# Sensor_Board_B.net
KiCad netlist of a schematic drawn in EAGLE
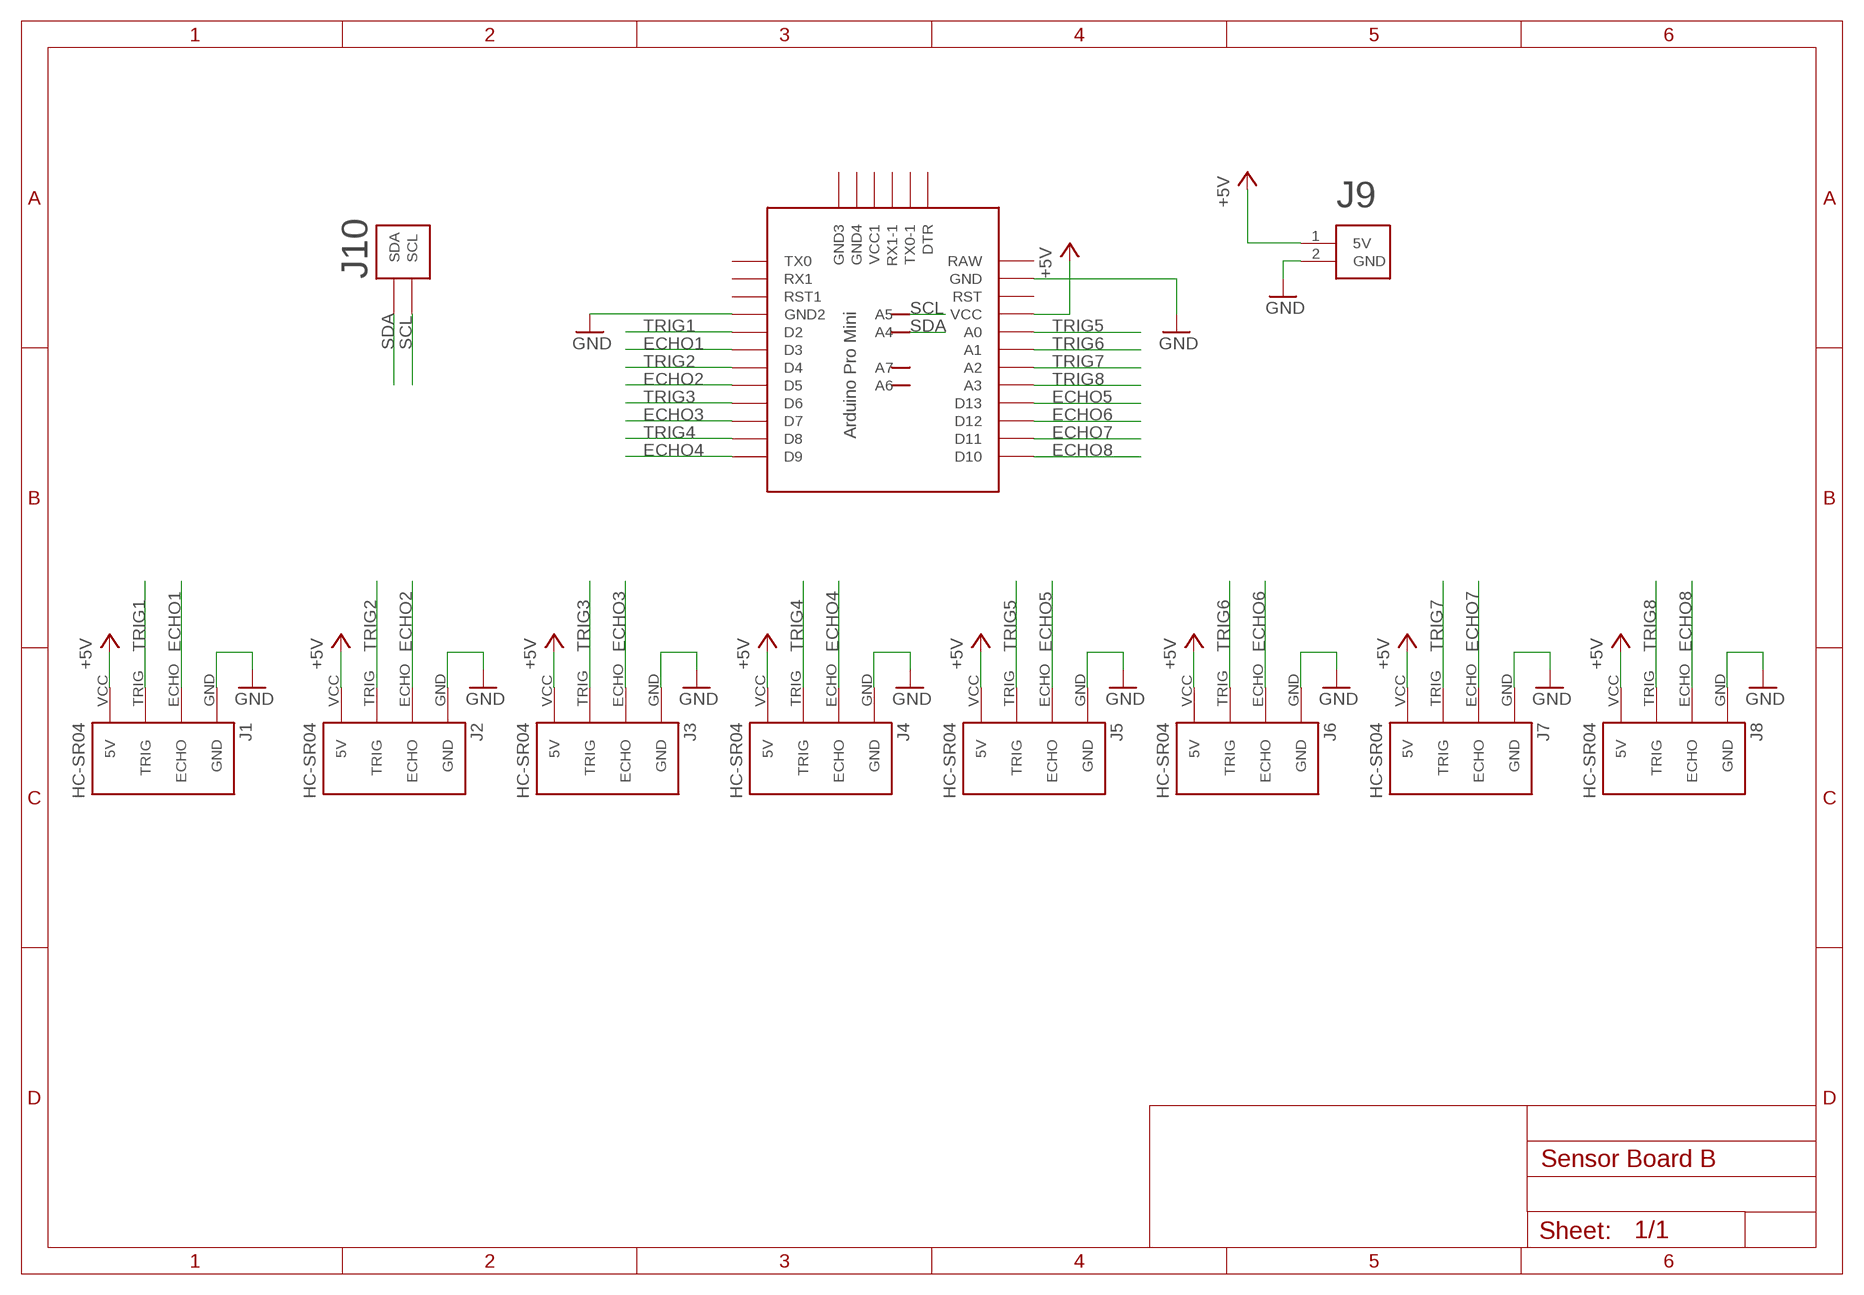
[diagram p0: schematic, sheet 1]

(export (version "E")
  (design (tool "Eeschema 10.0.6"))
  (components
    (comp (ref "J1")
      (value "HC-SR04")
      (footprint "eagle-import:HC-SR04_FOOTPRINT")
      (libsource (lib "eagle-import") (part "HC-SR04"))
    )
    (comp (ref "J2")
      (value "HC-SR04")
      (footprint "eagle-import:HC-SR04_FOOTPRINT")
      (libsource (lib "eagle-import") (part "HC-SR04"))
    )
    (comp (ref "J3")
      (value "HC-SR04")
      (footprint "eagle-import:HC-SR04_FOOTPRINT")
      (libsource (lib "eagle-import") (part "HC-SR04"))
    )
    (comp (ref "J4")
      (value "HC-SR04")
      (footprint "eagle-import:HC-SR04_FOOTPRINT")
      (libsource (lib "eagle-import") (part "HC-SR04"))
    )
    (comp (ref "J5")
      (value "HC-SR04")
      (footprint "eagle-import:HC-SR04_FOOTPRINT")
      (libsource (lib "eagle-import") (part "HC-SR04"))
    )
    (comp (ref "J6")
      (value "HC-SR04")
      (footprint "eagle-import:HC-SR04_FOOTPRINT")
      (libsource (lib "eagle-import") (part "HC-SR04"))
    )
    (comp (ref "J7")
      (value "HC-SR04")
      (footprint "eagle-import:HC-SR04_FOOTPRINT")
      (libsource (lib "eagle-import") (part "HC-SR04"))
    )
    (comp (ref "J8")
      (value "HC-SR04")
      (footprint "eagle-import:HC-SR04_FOOTPRINT")
      (libsource (lib "eagle-import") (part "HC-SR04"))
    )
    (comp (ref "J9")
      (value "POWER_CONNECTOR")
      (footprint "eagle-import:XH_CONNECTOR")
      (libsource (lib "eagle-import") (part "POWER_CONNECTOR"))
    )
    (comp (ref "J10")
      (value "I2C_CONNECTOR")
      (footprint "eagle-import:XH_CONNECTOR")
      (libsource (lib "eagle-import") (part "I2C_CONNECTOR"))
    )
    (comp (ref "U1")
      (value "PRO-MINI-2")
      (footprint "eagle-import:PRO-MINI-2")
      (libsource (lib "eagle-import") (part "PRO-MINI-2"))
    )
  )
  (nets
    (net (code "1") (name "+5V") (class "Default")
      (node (ref "J1") (pin "VCC") (pinfunction "5V_VCC") (pintype "bidirectional"))
      (node (ref "J2") (pin "VCC") (pinfunction "5V_VCC") (pintype "bidirectional"))
      (node (ref "J3") (pin "VCC") (pinfunction "5V_VCC") (pintype "bidirectional"))
      (node (ref "J4") (pin "VCC") (pinfunction "5V_VCC") (pintype "bidirectional"))
      (node (ref "J5") (pin "VCC") (pinfunction "5V_VCC") (pintype "bidirectional"))
      (node (ref "J6") (pin "VCC") (pinfunction "5V_VCC") (pintype "bidirectional"))
      (node (ref "J7") (pin "VCC") (pinfunction "5V_VCC") (pintype "bidirectional"))
      (node (ref "J8") (pin "VCC") (pinfunction "5V_VCC") (pintype "bidirectional"))
      (node (ref "J9") (pin "1") (pinfunction "5V_1") (pintype "power_in"))
      (node (ref "U1") (pin "VCC") (pinfunction "VCC_VCC") (pintype "bidirectional"))
    )
    (net (code "2") (name "/ECHO1") (class "Default")
      (node (ref "J1") (pin "ECHO") (pinfunction "ECHO_ECHO") (pintype "bidirectional"))
      (node (ref "U1") (pin "D3") (pinfunction "D3_D3") (pintype "bidirectional"))
    )
    (net (code "3") (name "/ECHO2") (class "Default")
      (node (ref "J2") (pin "ECHO") (pinfunction "ECHO_ECHO") (pintype "bidirectional"))
      (node (ref "U1") (pin "D5") (pinfunction "D5_D5") (pintype "bidirectional"))
    )
    (net (code "4") (name "/ECHO3") (class "Default")
      (node (ref "J3") (pin "ECHO") (pinfunction "ECHO_ECHO") (pintype "bidirectional"))
      (node (ref "U1") (pin "D7") (pinfunction "D7_D7") (pintype "bidirectional"))
    )
    (net (code "5") (name "/ECHO4") (class "Default")
      (node (ref "J4") (pin "ECHO") (pinfunction "ECHO_ECHO") (pintype "bidirectional"))
      (node (ref "U1") (pin "D9") (pinfunction "D9_D9") (pintype "bidirectional"))
    )
    (net (code "6") (name "/ECHO5") (class "Default")
      (node (ref "J5") (pin "ECHO") (pinfunction "ECHO_ECHO") (pintype "bidirectional"))
      (node (ref "U1") (pin "D13") (pinfunction "D13_D13") (pintype "bidirectional"))
    )
    (net (code "7") (name "/ECHO6") (class "Default")
      (node (ref "J6") (pin "ECHO") (pinfunction "ECHO_ECHO") (pintype "bidirectional"))
      (node (ref "U1") (pin "D12") (pinfunction "D12_D12") (pintype "bidirectional"))
    )
    (net (code "8") (name "/ECHO7") (class "Default")
      (node (ref "J7") (pin "ECHO") (pinfunction "ECHO_ECHO") (pintype "bidirectional"))
      (node (ref "U1") (pin "D11") (pinfunction "D11_D11") (pintype "bidirectional"))
    )
    (net (code "9") (name "/ECHO8") (class "Default")
      (node (ref "J8") (pin "ECHO") (pinfunction "ECHO_ECHO") (pintype "bidirectional"))
      (node (ref "U1") (pin "D10") (pinfunction "D10_D10") (pintype "bidirectional"))
    )
    (net (code "10") (name "/SCL") (class "Default")
      (node (ref "J10") (pin "1") (pinfunction "SCL_1") (pintype "bidirectional"))
      (node (ref "U1") (pin "A5") (pinfunction "A5_A5") (pintype "bidirectional"))
    )
    (net (code "11") (name "/SDA") (class "Default")
      (node (ref "J10") (pin "2") (pinfunction "SDA_2") (pintype "bidirectional"))
      (node (ref "U1") (pin "A4") (pinfunction "A4_A4") (pintype "bidirectional"))
    )
    (net (code "12") (name "/TRIG1") (class "Default")
      (node (ref "J1") (pin "TRIG") (pinfunction "TRIG_TRIG") (pintype "bidirectional"))
      (node (ref "U1") (pin "D2") (pinfunction "D2_D2") (pintype "bidirectional"))
    )
    (net (code "13") (name "/TRIG2") (class "Default")
      (node (ref "J2") (pin "TRIG") (pinfunction "TRIG_TRIG") (pintype "bidirectional"))
      (node (ref "U1") (pin "D4") (pinfunction "D4_D4") (pintype "bidirectional"))
    )
    (net (code "14") (name "/TRIG3") (class "Default")
      (node (ref "J3") (pin "TRIG") (pinfunction "TRIG_TRIG") (pintype "bidirectional"))
      (node (ref "U1") (pin "D6") (pinfunction "D6_D6") (pintype "bidirectional"))
    )
    (net (code "15") (name "/TRIG4") (class "Default")
      (node (ref "J4") (pin "TRIG") (pinfunction "TRIG_TRIG") (pintype "bidirectional"))
      (node (ref "U1") (pin "D8") (pinfunction "D8_D8") (pintype "bidirectional"))
    )
    (net (code "16") (name "/TRIG5") (class "Default")
      (node (ref "J5") (pin "TRIG") (pinfunction "TRIG_TRIG") (pintype "bidirectional"))
      (node (ref "U1") (pin "A0") (pinfunction "A0_A0") (pintype "bidirectional"))
    )
    (net (code "17") (name "/TRIG6") (class "Default")
      (node (ref "J6") (pin "TRIG") (pinfunction "TRIG_TRIG") (pintype "bidirectional"))
      (node (ref "U1") (pin "A1") (pinfunction "A1_A1") (pintype "bidirectional"))
    )
    (net (code "18") (name "/TRIG7") (class "Default")
      (node (ref "J7") (pin "TRIG") (pinfunction "TRIG_TRIG") (pintype "bidirectional"))
      (node (ref "U1") (pin "A2") (pinfunction "A2_A2") (pintype "bidirectional"))
    )
    (net (code "19") (name "/TRIG8") (class "Default")
      (node (ref "J8") (pin "TRIG") (pinfunction "TRIG_TRIG") (pintype "bidirectional"))
      (node (ref "U1") (pin "A3") (pinfunction "A3_A3") (pintype "bidirectional"))
    )
    (net (code "20") (name "GND") (class "Default")
      (node (ref "J1") (pin "GND") (pinfunction "GND_GND") (pintype "bidirectional"))
      (node (ref "J2") (pin "GND") (pinfunction "GND_GND") (pintype "bidirectional"))
      (node (ref "J3") (pin "GND") (pinfunction "GND_GND") (pintype "bidirectional"))
      (node (ref "J4") (pin "GND") (pinfunction "GND_GND") (pintype "bidirectional"))
      (node (ref "J5") (pin "GND") (pinfunction "GND_GND") (pintype "bidirectional"))
      (node (ref "J6") (pin "GND") (pinfunction "GND_GND") (pintype "bidirectional"))
      (node (ref "J7") (pin "GND") (pinfunction "GND_GND") (pintype "bidirectional"))
      (node (ref "J8") (pin "GND") (pinfunction "GND_GND") (pintype "bidirectional"))
      (node (ref "J9") (pin "2") (pinfunction "GND_2") (pintype "power_in"))
      (node (ref "U1") (pin "GND") (pinfunction "GND_GND") (pintype "bidirectional"))
      (node (ref "U1") (pin "GND1") (pinfunction "GND2_GND1") (pintype "bidirectional"))
    )
    (net (code "21") (name "unconnected-(U1-GND3-PadGND2)") (class "Default")
      (node (ref "U1") (pin "GND2") (pinfunction "GND3_GND2") (pintype "bidirectional"))
    )
    (net (code "22") (name "unconnected-(U1-GND4-PadGND3)") (class "Default")
      (node (ref "U1") (pin "GND3") (pinfunction "GND4_GND3") (pintype "bidirectional"))
    )
    (net (code "23") (name "unconnected-(U1-PadA6)") (class "Default")
      (node (ref "U1") (pin "A6") (pinfunction "A6_A6") (pintype "bidirectional"))
    )
    (net (code "24") (name "unconnected-(U1-PadA7)") (class "Default")
      (node (ref "U1") (pin "A7") (pinfunction "A7_A7") (pintype "bidirectional"))
    )
    (net (code "25") (name "unconnected-(U1-PadDTR)") (class "Default")
      (node (ref "U1") (pin "DTR") (pinfunction "DTR_DTR") (pintype "bidirectional"))
    )
    (net (code "26") (name "unconnected-(U1-PadRAW)") (class "Default")
      (node (ref "U1") (pin "RAW") (pinfunction "RAW_RAW") (pintype "bidirectional"))
    )
    (net (code "27") (name "unconnected-(U1-PadRST)") (class "Default")
      (node (ref "U1") (pin "RST") (pinfunction "RST_RST") (pintype "bidirectional"))
    )
    (net (code "28") (name "unconnected-(U1-PadRST1)") (class "Default")
      (node (ref "U1") (pin "RST1") (pinfunction "RST1_RST1") (pintype "bidirectional"))
    )
    (net (code "29") (name "unconnected-(U1-PadRX1)") (class "Default")
      (node (ref "U1") (pin "RX1") (pinfunction "RX1_RX1") (pintype "bidirectional"))
    )
    (net (code "30") (name "unconnected-(U1-PadRX1-1)") (class "Default")
      (node (ref "U1") (pin "RX1-1") (pinfunction "RX1-1_RX1-1") (pintype "bidirectional"))
    )
    (net (code "31") (name "unconnected-(U1-PadTX0)") (class "Default")
      (node (ref "U1") (pin "TX0") (pinfunction "TX0_TX0") (pintype "bidirectional"))
    )
    (net (code "32") (name "unconnected-(U1-PadTX0-1)") (class "Default")
      (node (ref "U1") (pin "TX0-1") (pinfunction "TX0-1_TX0-1") (pintype "bidirectional"))
    )
    (net (code "33") (name "unconnected-(U1-PadVCC1)") (class "Default")
      (node (ref "U1") (pin "VCC1") (pinfunction "VCC1_VCC1") (pintype "bidirectional"))
    )
  )
)
